# LeakSensor.net
KiCad netlist of a schematic drawn in EAGLE
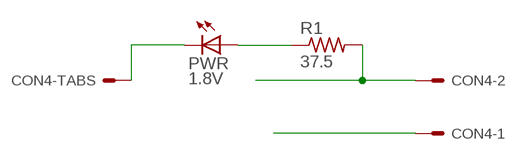
[diagram p0: schematic, sheet 1]

(export (version "E")
  (design (tool "Eeschema 10.0.6"))
  (components
    (comp (ref "CON4")
      (value "SM02B-GHS-TB")
      (footprint "eagle-import:SM02B-GHS-TB")
      (libsource (lib "eagle-import") (part "SM02B-GHS-TB"))
    )
    (comp (ref "PWR")
      (value "1.8V")
      (footprint "eagle-import:1206")
      (libsource (lib "eagle-import") (part "LEDSMT1206"))
    )
    (comp (ref "R1")
      (value "37.5")
      (footprint "eagle-import:R1206")
      (libsource (lib "eagle-import") (part "R-US_R1206"))
    )
  )
  (nets
    (net (code "1") (name "Net-(CON4B-S)") (class "Default")
      (node (ref "CON4") (pin "P$2") (pinfunction "S_P$2") (pintype "passive"))
      (node (ref "R1") (pin "2") (pinfunction "2_2") (pintype "passive"))
    )
    (net (code "2") (name "Net-(CON4C-S-PadP$3)") (class "Default")
      (node (ref "CON4") (pin "P$3") (pinfunction "S_P$3") (pintype "passive"))
      (node (ref "CON4") (pin "P$4") (pinfunction "S_P$4") (pintype "passive"))
      (node (ref "PWR") (pin "C") (pinfunction "C_C") (pintype "passive"))
    )
    (net (code "3") (name "Net-(PWR-PadA)") (class "Default")
      (node (ref "PWR") (pin "A") (pinfunction "A_A") (pintype "passive"))
      (node (ref "R1") (pin "1") (pinfunction "1_1") (pintype "passive"))
    )
    (net (code "4") (name "unconnected-(CON4A-S-PadP$1)") (class "Default")
      (node (ref "CON4") (pin "P$1") (pinfunction "S_P$1") (pintype "passive"))
    )
  )
)
